# diode_sampling_gate_xor_drive.net
KiCad netlist of a schematic drawn in EAGLE
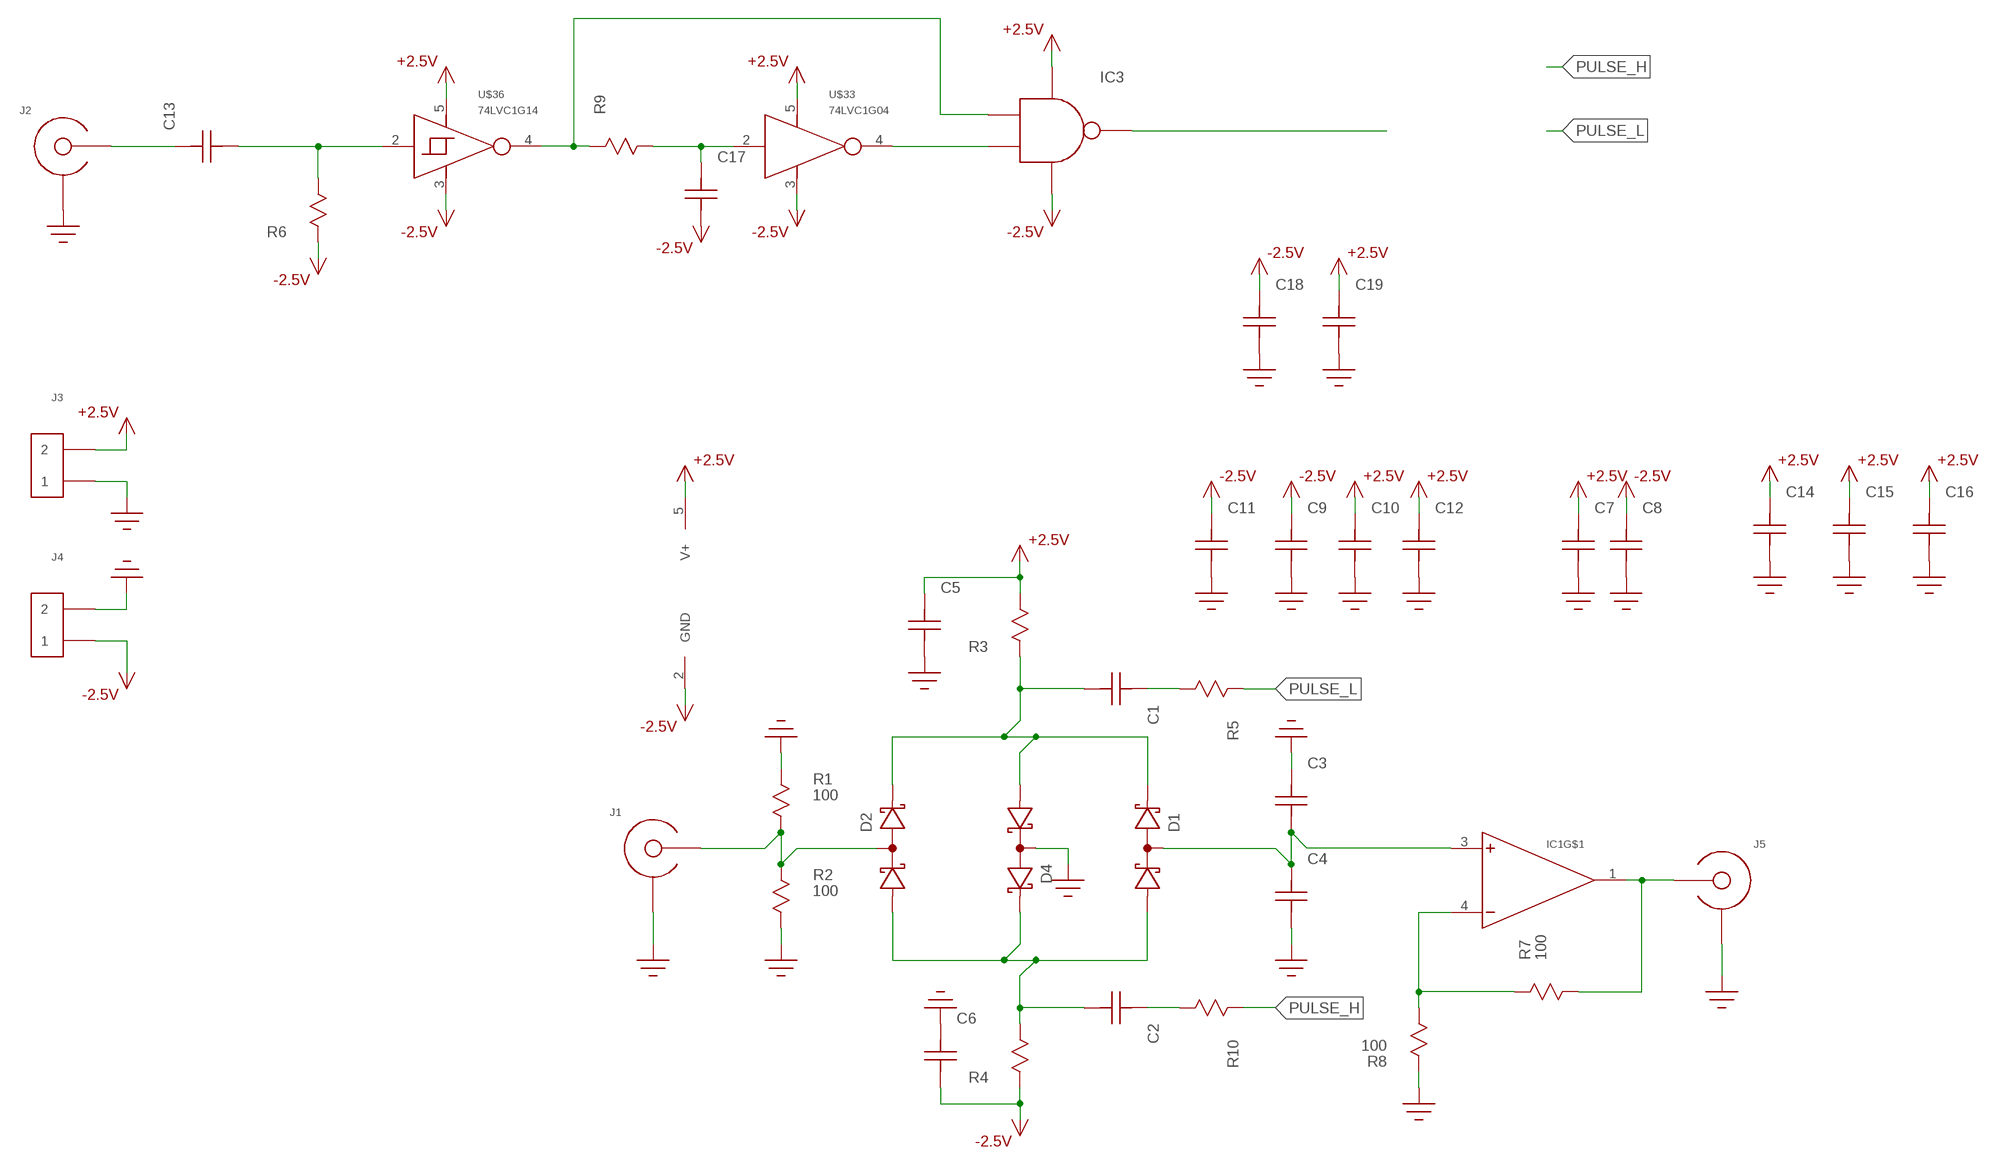
[diagram p0: schematic, sheet 1]

(export (version "E")
  (design (tool "Eeschema 10.0.6"))
  (components
    (comp (ref "C1")
      (value "C0603")
      (footprint "eagle-import:C0603")
      (libsource (lib "eagle-import") (part "C0603"))
    )
    (comp (ref "C2")
      (value "C0603")
      (footprint "eagle-import:C0603")
      (libsource (lib "eagle-import") (part "C0603"))
    )
    (comp (ref "C3")
      (value "C0603")
      (footprint "eagle-import:C0603")
      (libsource (lib "eagle-import") (part "C0603"))
    )
    (comp (ref "C4")
      (value "C0603")
      (footprint "eagle-import:C0603")
      (libsource (lib "eagle-import") (part "C0603"))
    )
    (comp (ref "C5")
      (value "C0603")
      (footprint "eagle-import:C0603")
      (libsource (lib "eagle-import") (part "C0603"))
    )
    (comp (ref "C6")
      (value "C0603")
      (footprint "eagle-import:C0603")
      (libsource (lib "eagle-import") (part "C0603"))
    )
    (comp (ref "C7") (value "C") (footprint "eagle-import:C0402") (libsource (lib "eagle-import") (part "C")))
    (comp (ref "C8") (value "C") (footprint "eagle-import:C0402") (libsource (lib "eagle-import") (part "C")))
    (comp (ref "C9")
      (value "C0603")
      (footprint "eagle-import:C0603")
      (libsource (lib "eagle-import") (part "C0603"))
    )
    (comp (ref "C10")
      (value "C0603")
      (footprint "eagle-import:C0603")
      (libsource (lib "eagle-import") (part "C0603"))
    )
    (comp (ref "C11")
      (value "C0805")
      (footprint "eagle-import:0805")
      (libsource (lib "eagle-import") (part "C0805"))
    )
    (comp (ref "C12")
      (value "C0805")
      (footprint "eagle-import:0805")
      (libsource (lib "eagle-import") (part "C0805"))
    )
    (comp (ref "C13")
      (value "C0603")
      (footprint "eagle-import:C0603")
      (libsource (lib "eagle-import") (part "C0603"))
    )
    (comp (ref "C14")
      (value "C0603")
      (footprint "eagle-import:C0603")
      (libsource (lib "eagle-import") (part "C0603"))
    )
    (comp (ref "C15")
      (value "C0603")
      (footprint "eagle-import:C0603")
      (libsource (lib "eagle-import") (part "C0603"))
    )
    (comp (ref "C16")
      (value "C0603")
      (footprint "eagle-import:C0603")
      (libsource (lib "eagle-import") (part "C0603"))
    )
    (comp (ref "C17")
      (value "C0603")
      (footprint "eagle-import:C0603")
      (libsource (lib "eagle-import") (part "C0603"))
    )
    (comp (ref "C18")
      (value "C0805")
      (footprint "eagle-import:0805")
      (libsource (lib "eagle-import") (part "C0805"))
    )
    (comp (ref "C19")
      (value "C0805")
      (footprint "eagle-import:0805")
      (libsource (lib "eagle-import") (part "C0805"))
    )
    (comp (ref "D1")
      (value "BAS40-04")
      (footprint "eagle-import:SOT-23")
      (libsource (lib "eagle-import") (part "BAS40-04"))
    )
    (comp (ref "D2")
      (value "BAS40-04")
      (footprint "eagle-import:SOT-23")
      (libsource (lib "eagle-import") (part "BAS40-04"))
    )
    (comp (ref "D4")
      (value "BAS40-04")
      (footprint "eagle-import:SOT-23")
      (libsource (lib "eagle-import") (part "BAS40-04"))
    )
    (comp (ref "IC1")
      (value "MCP6V81")
      (footprint "eagle-import:SOT23-5")
      (libsource (lib "eagle-import") (part "MCP6V81"))
    )
    (comp (ref "IC3")
      (value "74LVC1G00")
      (footprint "eagle-import:SOT23-5")
      (libsource (lib "eagle-import") (part "74LVC1G00"))
    )
    (comp (ref "J1")
      (value "EDGE_LAUNCH_JACK")
      (footprint "eagle-import:EDGE_LAUNCH_RF_CON")
      (libsource (lib "eagle-import") (part "EDGE_LAUNCH_JACK"))
    )
    (comp (ref "J2")
      (value "EDGE_LAUNCH_JACK")
      (footprint "eagle-import:EDGE_LAUNCH_RF_CON")
      (libsource (lib "eagle-import") (part "EDGE_LAUNCH_JACK"))
    )
    (comp (ref "J3")
      (value "HEADER_2PIN")
      (footprint "eagle-import:HEADER_2PIN")
      (libsource (lib "eagle-import") (part "HEADER_2PIN"))
    )
    (comp (ref "J4")
      (value "HEADER_2PIN")
      (footprint "eagle-import:HEADER_2PIN")
      (libsource (lib "eagle-import") (part "HEADER_2PIN"))
    )
    (comp (ref "J5")
      (value "EDGE_LAUNCH_JACK")
      (footprint "eagle-import:EDGE_LAUNCH_RF_CON")
      (libsource (lib "eagle-import") (part "EDGE_LAUNCH_JACK"))
    )
    (comp (ref "R1")
      (value "100")
      (footprint "eagle-import:R0805")
      (libsource (lib "eagle-import") (part "R0805"))
    )
    (comp (ref "R2")
      (value "100")
      (footprint "eagle-import:R0805")
      (libsource (lib "eagle-import") (part "R0805"))
    )
    (comp (ref "R3")
      (value "R0603")
      (footprint "eagle-import:R0603")
      (libsource (lib "eagle-import") (part "R0603"))
    )
    (comp (ref "R4")
      (value "R0603")
      (footprint "eagle-import:R0603")
      (libsource (lib "eagle-import") (part "R0603"))
    )
    (comp (ref "R5")
      (value "R0603")
      (footprint "eagle-import:R0603")
      (libsource (lib "eagle-import") (part "R0603"))
    )
    (comp (ref "R6")
      (value "R0603")
      (footprint "eagle-import:R0603")
      (libsource (lib "eagle-import") (part "R0603"))
    )
    (comp (ref "R7")
      (value "100")
      (footprint "eagle-import:R0603")
      (libsource (lib "eagle-import") (part "R0603"))
    )
    (comp (ref "R8")
      (value "100")
      (footprint "eagle-import:R0603")
      (libsource (lib "eagle-import") (part "R0603"))
    )
    (comp (ref "R9")
      (value "R0603")
      (footprint "eagle-import:R0603")
      (libsource (lib "eagle-import") (part "R0603"))
    )
    (comp (ref "R10")
      (value "R0603")
      (footprint "eagle-import:R0603")
      (libsource (lib "eagle-import") (part "R0603"))
    )
    (comp (ref "U$33")
      (value "74LVC1G04")
      (footprint "eagle-import:SOT23-5")
      (libsource (lib "eagle-import") (part "74LVC1G04"))
    )
    (comp (ref "U$36")
      (value "74LVC1G14")
      (footprint "eagle-import:SOT23-5")
      (libsource (lib "eagle-import") (part "74LVC1G14"))
    )
  )
  (nets
    (net (code "1") (name "+2.5V") (class "Default")
      (node (ref "C10") (pin "P$2") (pinfunction "P$2_P$2") (pintype "bidirectional"))
      (node (ref "C12") (pin "P$2") (pinfunction "P$2_P$2") (pintype "bidirectional"))
      (node (ref "C14") (pin "P$2") (pinfunction "P$2_P$2") (pintype "bidirectional"))
      (node (ref "C15") (pin "P$2") (pinfunction "P$2_P$2") (pintype "bidirectional"))
      (node (ref "C16") (pin "P$2") (pinfunction "P$2_P$2") (pintype "bidirectional"))
      (node (ref "C19") (pin "P$2") (pinfunction "P$2_P$2") (pintype "bidirectional"))
      (node (ref "C5") (pin "P$2") (pinfunction "P$2_P$2") (pintype "bidirectional"))
      (node (ref "C7") (pin "2") (pinfunction "P$2_2") (pintype "bidirectional"))
      (node (ref "IC1") (pin "5") (pinfunction "V+_5") (pintype "bidirectional"))
      (node (ref "IC3") (pin "5") (pinfunction "VCC_5") (pintype "bidirectional"))
      (node (ref "J3") (pin "2") (pinfunction "2_2") (pintype "bidirectional"))
      (node (ref "R3") (pin "P$2") (pinfunction "P$4_P$2") (pintype "bidirectional"))
      (node (ref "U$33") (pin "5") (pinfunction "VCC_5") (pintype "bidirectional"))
      (node (ref "U$36") (pin "5") (pinfunction "VCC_5") (pintype "bidirectional"))
    )
    (net (code "2") (name "-2.5V") (class "Default")
      (node (ref "C11") (pin "P$2") (pinfunction "P$2_P$2") (pintype "bidirectional"))
      (node (ref "C17") (pin "P$1") (pinfunction "P$1_P$1") (pintype "bidirectional"))
      (node (ref "C18") (pin "P$2") (pinfunction "P$2_P$2") (pintype "bidirectional"))
      (node (ref "C6") (pin "P$1") (pinfunction "P$1_P$1") (pintype "bidirectional"))
      (node (ref "C8") (pin "2") (pinfunction "P$2_2") (pintype "bidirectional"))
      (node (ref "C9") (pin "P$2") (pinfunction "P$2_P$2") (pintype "bidirectional"))
      (node (ref "IC1") (pin "2") (pinfunction "GND_2") (pintype "bidirectional"))
      (node (ref "IC3") (pin "3") (pinfunction "GND_3") (pintype "bidirectional"))
      (node (ref "J4") (pin "1") (pinfunction "1_1") (pintype "bidirectional"))
      (node (ref "R4") (pin "P$1") (pinfunction "P$3_P$1") (pintype "bidirectional"))
      (node (ref "R6") (pin "P$1") (pinfunction "P$3_P$1") (pintype "bidirectional"))
      (node (ref "U$33") (pin "3") (pinfunction "GND_3") (pintype "bidirectional"))
      (node (ref "U$36") (pin "3") (pinfunction "GND_3") (pintype "bidirectional"))
    )
    (net (code "3") (name "GND") (class "Default")
      (node (ref "C10") (pin "P$1") (pinfunction "P$1_P$1") (pintype "bidirectional"))
      (node (ref "C11") (pin "P$1") (pinfunction "P$1_P$1") (pintype "bidirectional"))
      (node (ref "C12") (pin "P$1") (pinfunction "P$1_P$1") (pintype "bidirectional"))
      (node (ref "C14") (pin "P$1") (pinfunction "P$1_P$1") (pintype "bidirectional"))
      (node (ref "C15") (pin "P$1") (pinfunction "P$1_P$1") (pintype "bidirectional"))
      (node (ref "C16") (pin "P$1") (pinfunction "P$1_P$1") (pintype "bidirectional"))
      (node (ref "C18") (pin "P$1") (pinfunction "P$1_P$1") (pintype "bidirectional"))
      (node (ref "C19") (pin "P$1") (pinfunction "P$1_P$1") (pintype "bidirectional"))
      (node (ref "C3") (pin "P$2") (pinfunction "P$2_P$2") (pintype "bidirectional"))
      (node (ref "C4") (pin "P$1") (pinfunction "P$1_P$1") (pintype "bidirectional"))
      (node (ref "C5") (pin "P$1") (pinfunction "P$1_P$1") (pintype "bidirectional"))
      (node (ref "C6") (pin "P$2") (pinfunction "P$2_P$2") (pintype "bidirectional"))
      (node (ref "C7") (pin "1") (pinfunction "P$1_1") (pintype "bidirectional"))
      (node (ref "C8") (pin "1") (pinfunction "P$1_1") (pintype "bidirectional"))
      (node (ref "C9") (pin "P$1") (pinfunction "P$1_P$1") (pintype "bidirectional"))
      (node (ref "D4") (pin "3") (pinfunction "COMMON_3") (pintype "bidirectional"))
      (node (ref "J1") (pin "GND@1") (pinfunction "SHIELD_GND@1") (pintype "bidirectional"))
      (node (ref "J1") (pin "GND@10") (pinfunction "SHIELD_GND@10") (pintype "bidirectional"))
      (node (ref "J1") (pin "GND@11") (pinfunction "SHIELD_GND@11") (pintype "bidirectional"))
      (node (ref "J1") (pin "GND@12") (pinfunction "SHIELD_GND@12") (pintype "bidirectional"))
      (node (ref "J1") (pin "GND@2") (pinfunction "SHIELD_GND@2") (pintype "bidirectional"))
      (node (ref "J1") (pin "GND@3") (pinfunction "SHIELD_GND@3") (pintype "bidirectional"))
      (node (ref "J1") (pin "GND@4") (pinfunction "SHIELD_GND@4") (pintype "bidirectional"))
      (node (ref "J1") (pin "GND@5") (pinfunction "SHIELD_GND@5") (pintype "bidirectional"))
      (node (ref "J1") (pin "GND@6") (pinfunction "SHIELD_GND@6") (pintype "bidirectional"))
      (node (ref "J1") (pin "GND@7") (pinfunction "SHIELD_GND@7") (pintype "bidirectional"))
      (node (ref "J1") (pin "GND@8") (pinfunction "SHIELD_GND@8") (pintype "bidirectional"))
      (node (ref "J1") (pin "GND@9") (pinfunction "SHIELD_GND@9") (pintype "bidirectional"))
      (node (ref "J1") (pin "SHIELD@1") (pinfunction "SHIELD_SHIELD@1") (pintype "bidirectional"))
      (node (ref "J1") (pin "SHIELD@2") (pinfunction "SHIELD_SHIELD@2") (pintype "bidirectional"))
      (node (ref "J2") (pin "GND@1") (pinfunction "SHIELD_GND@1") (pintype "bidirectional"))
      (node (ref "J2") (pin "GND@10") (pinfunction "SHIELD_GND@10") (pintype "bidirectional"))
      (node (ref "J2") (pin "GND@11") (pinfunction "SHIELD_GND@11") (pintype "bidirectional"))
      (node (ref "J2") (pin "GND@12") (pinfunction "SHIELD_GND@12") (pintype "bidirectional"))
      (node (ref "J2") (pin "GND@2") (pinfunction "SHIELD_GND@2") (pintype "bidirectional"))
      (node (ref "J2") (pin "GND@3") (pinfunction "SHIELD_GND@3") (pintype "bidirectional"))
      (node (ref "J2") (pin "GND@4") (pinfunction "SHIELD_GND@4") (pintype "bidirectional"))
      (node (ref "J2") (pin "GND@5") (pinfunction "SHIELD_GND@5") (pintype "bidirectional"))
      (node (ref "J2") (pin "GND@6") (pinfunction "SHIELD_GND@6") (pintype "bidirectional"))
      (node (ref "J2") (pin "GND@7") (pinfunction "SHIELD_GND@7") (pintype "bidirectional"))
      (node (ref "J2") (pin "GND@8") (pinfunction "SHIELD_GND@8") (pintype "bidirectional"))
      (node (ref "J2") (pin "GND@9") (pinfunction "SHIELD_GND@9") (pintype "bidirectional"))
      (node (ref "J2") (pin "SHIELD@1") (pinfunction "SHIELD_SHIELD@1") (pintype "bidirectional"))
      (node (ref "J2") (pin "SHIELD@2") (pinfunction "SHIELD_SHIELD@2") (pintype "bidirectional"))
      (node (ref "J3") (pin "1") (pinfunction "1_1") (pintype "bidirectional"))
      (node (ref "J4") (pin "2") (pinfunction "2_2") (pintype "bidirectional"))
      (node (ref "J5") (pin "GND@1") (pinfunction "SHIELD_GND@1") (pintype "bidirectional"))
      (node (ref "J5") (pin "GND@10") (pinfunction "SHIELD_GND@10") (pintype "bidirectional"))
      (node (ref "J5") (pin "GND@11") (pinfunction "SHIELD_GND@11") (pintype "bidirectional"))
      (node (ref "J5") (pin "GND@12") (pinfunction "SHIELD_GND@12") (pintype "bidirectional"))
      (node (ref "J5") (pin "GND@2") (pinfunction "SHIELD_GND@2") (pintype "bidirectional"))
      (node (ref "J5") (pin "GND@3") (pinfunction "SHIELD_GND@3") (pintype "bidirectional"))
      (node (ref "J5") (pin "GND@4") (pinfunction "SHIELD_GND@4") (pintype "bidirectional"))
      (node (ref "J5") (pin "GND@5") (pinfunction "SHIELD_GND@5") (pintype "bidirectional"))
      (node (ref "J5") (pin "GND@6") (pinfunction "SHIELD_GND@6") (pintype "bidirectional"))
      (node (ref "J5") (pin "GND@7") (pinfunction "SHIELD_GND@7") (pintype "bidirectional"))
      (node (ref "J5") (pin "GND@8") (pinfunction "SHIELD_GND@8") (pintype "bidirectional"))
      (node (ref "J5") (pin "GND@9") (pinfunction "SHIELD_GND@9") (pintype "bidirectional"))
      (node (ref "J5") (pin "SHIELD@1") (pinfunction "SHIELD_SHIELD@1") (pintype "bidirectional"))
      (node (ref "J5") (pin "SHIELD@2") (pinfunction "SHIELD_SHIELD@2") (pintype "bidirectional"))
      (node (ref "R1") (pin "P$1") (pinfunction "P$3_P$1") (pintype "bidirectional"))
      (node (ref "R2") (pin "P$2") (pinfunction "P$4_P$2") (pintype "bidirectional"))
      (node (ref "R8") (pin "P$1") (pinfunction "P$3_P$1") (pintype "bidirectional"))
    )
    (net (code "4") (name "Net-(C13-PadP$2)") (class "Default")
      (node (ref "C13") (pin "P$2") (pinfunction "P$2_P$2") (pintype "bidirectional"))
      (node (ref "J2") (pin "CENTER") (pinfunction "CENTER_CENTER") (pintype "bidirectional"))
    )
    (net (code "5") (name "Net-(D1-ANODE)") (class "Default")
      (node (ref "C2") (pin "P$1") (pinfunction "P$1_P$1") (pintype "bidirectional"))
      (node (ref "D1") (pin "1") (pinfunction "ANODE_1") (pintype "bidirectional"))
      (node (ref "D2") (pin "1") (pinfunction "ANODE_1") (pintype "bidirectional"))
      (node (ref "D4") (pin "2") (pinfunction "CATHODE_2") (pintype "bidirectional"))
      (node (ref "R4") (pin "P$2") (pinfunction "P$4_P$2") (pintype "bidirectional"))
    )
    (net (code "6") (name "Net-(D1-CATHODE)") (class "Default")
      (node (ref "C1") (pin "P$1") (pinfunction "P$1_P$1") (pintype "bidirectional"))
      (node (ref "D1") (pin "2") (pinfunction "CATHODE_2") (pintype "bidirectional"))
      (node (ref "D2") (pin "2") (pinfunction "CATHODE_2") (pintype "bidirectional"))
      (node (ref "D4") (pin "1") (pinfunction "ANODE_1") (pintype "bidirectional"))
      (node (ref "R3") (pin "P$1") (pinfunction "P$3_P$1") (pintype "bidirectional"))
    )
    (net (code "7") (name "Net-(D1-COMMON)") (class "Default")
      (node (ref "C3") (pin "P$1") (pinfunction "P$1_P$1") (pintype "bidirectional"))
      (node (ref "C4") (pin "P$2") (pinfunction "P$2_P$2") (pintype "bidirectional"))
      (node (ref "D1") (pin "3") (pinfunction "COMMON_3") (pintype "bidirectional"))
      (node (ref "IC1") (pin "3") (pinfunction "+_3") (pintype "bidirectional"))
    )
    (net (code "8") (name "Net-(D2-COMMON)") (class "Default")
      (node (ref "D2") (pin "3") (pinfunction "COMMON_3") (pintype "bidirectional"))
      (node (ref "J1") (pin "CENTER") (pinfunction "CENTER_CENTER") (pintype "bidirectional"))
      (node (ref "R1") (pin "P$2") (pinfunction "P$4_P$2") (pintype "bidirectional"))
      (node (ref "R2") (pin "P$1") (pinfunction "P$3_P$1") (pintype "bidirectional"))
    )
    (net (code "9") (name "Net-(IC1A--)") (class "Default")
      (node (ref "IC1") (pin "4") (pinfunction "-_4") (pintype "bidirectional"))
      (node (ref "R7") (pin "P$1") (pinfunction "P$3_P$1") (pintype "bidirectional"))
      (node (ref "R8") (pin "P$2") (pinfunction "P$4_P$2") (pintype "bidirectional"))
    )
    (net (code "10") (name "Net-(IC1A-OUT)") (class "Default")
      (node (ref "IC1") (pin "1") (pinfunction "OUT_1") (pintype "bidirectional"))
      (node (ref "J5") (pin "CENTER") (pinfunction "CENTER_CENTER") (pintype "bidirectional"))
      (node (ref "R7") (pin "P$2") (pinfunction "P$4_P$2") (pintype "bidirectional"))
    )
    (net (code "11") (name "Net-(IC3-A)") (class "Default")
      (node (ref "IC3") (pin "2") (pinfunction "A_2") (pintype "bidirectional"))
      (node (ref "R9") (pin "P$1") (pinfunction "P$3_P$1") (pintype "bidirectional"))
      (node (ref "U$36") (pin "4") (pinfunction "OUT_4") (pintype "bidirectional"))
    )
    (net (code "12") (name "Net-(IC3-B)") (class "Default")
      (node (ref "IC3") (pin "1") (pinfunction "B_1") (pintype "bidirectional"))
      (node (ref "U$33") (pin "4") (pinfunction "OUT_4") (pintype "bidirectional"))
    )
    (net (code "13") (name "Net-(R5-P$4)") (class "Default")
      (node (ref "C1") (pin "P$2") (pinfunction "P$2_P$2") (pintype "bidirectional"))
      (node (ref "R5") (pin "P$2") (pinfunction "P$4_P$2") (pintype "bidirectional"))
    )
    (net (code "14") (name "Net-(R6-P$4)") (class "Default")
      (node (ref "C13") (pin "P$1") (pinfunction "P$1_P$1") (pintype "bidirectional"))
      (node (ref "R6") (pin "P$2") (pinfunction "P$4_P$2") (pintype "bidirectional"))
      (node (ref "U$36") (pin "2") (pinfunction "IN_2") (pintype "bidirectional"))
    )
    (net (code "15") (name "Net-(R9-P$4)") (class "Default")
      (node (ref "C17") (pin "P$2") (pinfunction "P$2_P$2") (pintype "bidirectional"))
      (node (ref "R9") (pin "P$2") (pinfunction "P$4_P$2") (pintype "bidirectional"))
      (node (ref "U$33") (pin "2") (pinfunction "IN_2") (pintype "bidirectional"))
    )
    (net (code "16") (name "Net-(R10-P$4)") (class "Default")
      (node (ref "C2") (pin "P$2") (pinfunction "P$2_P$2") (pintype "bidirectional"))
      (node (ref "R10") (pin "P$2") (pinfunction "P$4_P$2") (pintype "bidirectional"))
    )
    (net (code "17") (name "PULSE_H") (class "Default")
      (node (ref "R10") (pin "P$1") (pinfunction "P$3_P$1") (pintype "bidirectional"))
    )
    (net (code "18") (name "PULSE_L") (class "Default")
      (node (ref "R5") (pin "P$1") (pinfunction "P$3_P$1") (pintype "bidirectional"))
    )
    (net (code "19") (name "unconnected-(IC3-Y-Pad4)") (class "Default")
      (node (ref "IC3") (pin "4") (pinfunction "Y_4") (pintype "bidirectional"))
    )
  )
)
